# karmacontroller.net
KiCad netlist of a schematic drawn in EAGLE
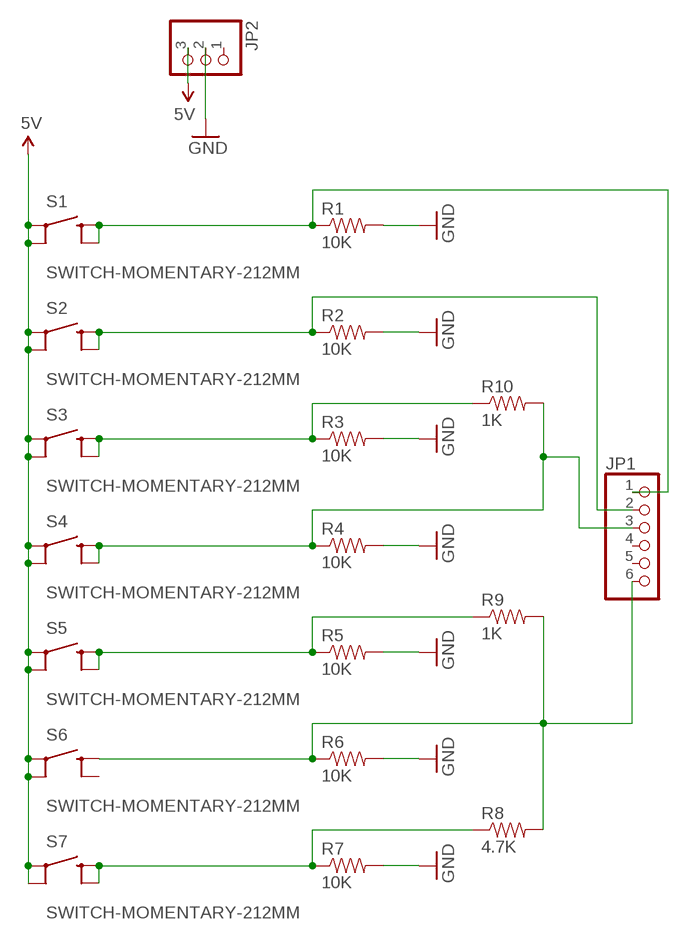
[diagram p0: schematic, sheet 1]

(export (version "E")
  (design (tool "Eeschema 10.0.6"))
  (components
    (comp (ref "JP1")
      (value "PINHD-1X6")
      (footprint "eagle-import:1X06")
      (libsource (lib "eagle-import") (part "PINHD-1X6"))
    )
    (comp (ref "JP2")
      (value "PINHD-1X3")
      (footprint "eagle-import:1X03")
      (libsource (lib "eagle-import") (part "PINHD-1X3"))
    )
    (comp (ref "R1")
      (value "10K")
      (footprint "eagle-import:AXIAL-0.3")
      (libsource (lib "eagle-import") (part "RESISTORAXIAL-0.3"))
    )
    (comp (ref "R2")
      (value "10K")
      (footprint "eagle-import:AXIAL-0.3")
      (libsource (lib "eagle-import") (part "RESISTORAXIAL-0.3"))
    )
    (comp (ref "R3")
      (value "10K")
      (footprint "eagle-import:AXIAL-0.3")
      (libsource (lib "eagle-import") (part "RESISTORAXIAL-0.3"))
    )
    (comp (ref "R4")
      (value "10K")
      (footprint "eagle-import:AXIAL-0.3")
      (libsource (lib "eagle-import") (part "RESISTORAXIAL-0.3"))
    )
    (comp (ref "R5")
      (value "10K")
      (footprint "eagle-import:AXIAL-0.3")
      (libsource (lib "eagle-import") (part "RESISTORAXIAL-0.3"))
    )
    (comp (ref "R6")
      (value "10K")
      (footprint "eagle-import:AXIAL-0.3")
      (libsource (lib "eagle-import") (part "RESISTORAXIAL-0.3"))
    )
    (comp (ref "R7")
      (value "10K")
      (footprint "eagle-import:AXIAL-0.3")
      (libsource (lib "eagle-import") (part "RESISTORAXIAL-0.3"))
    )
    (comp (ref "R8")
      (value "4.7K")
      (footprint "eagle-import:AXIAL-0.3")
      (libsource (lib "eagle-import") (part "RESISTORAXIAL-0.3"))
    )
    (comp (ref "R9")
      (value "1K")
      (footprint "eagle-import:AXIAL-0.3")
      (libsource (lib "eagle-import") (part "RESISTORAXIAL-0.3"))
    )
    (comp (ref "R10")
      (value "1K")
      (footprint "eagle-import:AXIAL-0.3")
      (libsource (lib "eagle-import") (part "RESISTORAXIAL-0.3"))
    )
    (comp (ref "S1")
      (value "SWITCH-MOMENTARY-212MM")
      (footprint "eagle-import:TACTILE-PTH-12MM")
      (libsource (lib "eagle-import") (part "SWITCH-MOMENTARY-212MM"))
    )
    (comp (ref "S2")
      (value "SWITCH-MOMENTARY-212MM")
      (footprint "eagle-import:TACTILE-PTH-12MM")
      (libsource (lib "eagle-import") (part "SWITCH-MOMENTARY-212MM"))
    )
    (comp (ref "S3")
      (value "SWITCH-MOMENTARY-212MM")
      (footprint "eagle-import:TACTILE-PTH-12MM")
      (libsource (lib "eagle-import") (part "SWITCH-MOMENTARY-212MM"))
    )
    (comp (ref "S4")
      (value "SWITCH-MOMENTARY-212MM")
      (footprint "eagle-import:TACTILE-PTH-12MM")
      (libsource (lib "eagle-import") (part "SWITCH-MOMENTARY-212MM"))
    )
    (comp (ref "S5")
      (value "SWITCH-MOMENTARY-212MM")
      (footprint "eagle-import:TACTILE-PTH-12MM")
      (libsource (lib "eagle-import") (part "SWITCH-MOMENTARY-212MM"))
    )
    (comp (ref "S6")
      (value "SWITCH-MOMENTARY-212MM")
      (footprint "eagle-import:TACTILE-PTH-12MM")
      (libsource (lib "eagle-import") (part "SWITCH-MOMENTARY-212MM"))
    )
    (comp (ref "S7")
      (value "SWITCH-MOMENTARY-212MM")
      (footprint "eagle-import:TACTILE-PTH-12MM")
      (libsource (lib "eagle-import") (part "SWITCH-MOMENTARY-212MM"))
    )
  )
  (nets
    (net (code "1") (name "5V") (class "Default")
      (node (ref "JP2") (pin "3") (pinfunction "3_3") (pintype "passive"))
      (node (ref "S1") (pin "1") (pinfunction "1_1") (pintype "passive"))
      (node (ref "S1") (pin "2") (pinfunction "1'_2") (pintype "passive"))
      (node (ref "S2") (pin "1") (pinfunction "1_1") (pintype "passive"))
      (node (ref "S2") (pin "2") (pinfunction "1'_2") (pintype "passive"))
      (node (ref "S3") (pin "1") (pinfunction "1_1") (pintype "passive"))
      (node (ref "S3") (pin "2") (pinfunction "1'_2") (pintype "passive"))
      (node (ref "S4") (pin "1") (pinfunction "1_1") (pintype "passive"))
      (node (ref "S4") (pin "2") (pinfunction "1'_2") (pintype "passive"))
      (node (ref "S5") (pin "1") (pinfunction "1_1") (pintype "passive"))
      (node (ref "S5") (pin "2") (pinfunction "1'_2") (pintype "passive"))
      (node (ref "S6") (pin "1") (pinfunction "1_1") (pintype "passive"))
      (node (ref "S6") (pin "2") (pinfunction "1'_2") (pintype "passive"))
      (node (ref "S7") (pin "1") (pinfunction "1_1") (pintype "passive"))
      (node (ref "S7") (pin "2") (pinfunction "1'_2") (pintype "passive"))
    )
    (net (code "2") (name "GND") (class "Default")
      (node (ref "JP2") (pin "2") (pinfunction "2_2") (pintype "passive"))
      (node (ref "R1") (pin "P$2") (pinfunction "2_P$2") (pintype "passive"))
      (node (ref "R2") (pin "P$2") (pinfunction "2_P$2") (pintype "passive"))
      (node (ref "R3") (pin "P$2") (pinfunction "2_P$2") (pintype "passive"))
      (node (ref "R4") (pin "P$2") (pinfunction "2_P$2") (pintype "passive"))
      (node (ref "R5") (pin "P$2") (pinfunction "2_P$2") (pintype "passive"))
      (node (ref "R6") (pin "P$2") (pinfunction "2_P$2") (pintype "passive"))
      (node (ref "R7") (pin "P$2") (pinfunction "2_P$2") (pintype "passive"))
    )
    (net (code "3") (name "Net-(R1-1)") (class "Default")
      (node (ref "JP1") (pin "1") (pinfunction "1_1") (pintype "passive"))
      (node (ref "R1") (pin "P$1") (pinfunction "1_P$1") (pintype "passive"))
      (node (ref "S1") (pin "3") (pinfunction "2_3") (pintype "passive"))
      (node (ref "S1") (pin "4") (pinfunction "2'_4") (pintype "passive"))
    )
    (net (code "4") (name "Net-(R2-1)") (class "Default")
      (node (ref "JP1") (pin "2") (pinfunction "2_2") (pintype "passive"))
      (node (ref "R2") (pin "P$1") (pinfunction "1_P$1") (pintype "passive"))
      (node (ref "S2") (pin "3") (pinfunction "2_3") (pintype "passive"))
      (node (ref "S2") (pin "4") (pinfunction "2'_4") (pintype "passive"))
    )
    (net (code "5") (name "Net-(R5-1)") (class "Default")
      (node (ref "R5") (pin "P$1") (pinfunction "1_P$1") (pintype "passive"))
      (node (ref "R9") (pin "P$1") (pinfunction "1_P$1") (pintype "passive"))
      (node (ref "S5") (pin "3") (pinfunction "2_3") (pintype "passive"))
      (node (ref "S5") (pin "4") (pinfunction "2'_4") (pintype "passive"))
    )
    (net (code "6") (name "Net-(R6-1)") (class "Default")
      (node (ref "JP1") (pin "6") (pinfunction "6_6") (pintype "passive"))
      (node (ref "R6") (pin "P$1") (pinfunction "1_P$1") (pintype "passive"))
      (node (ref "R8") (pin "P$2") (pinfunction "2_P$2") (pintype "passive"))
      (node (ref "R9") (pin "P$2") (pinfunction "2_P$2") (pintype "passive"))
      (node (ref "S6") (pin "3") (pinfunction "2_3") (pintype "passive"))
    )
    (net (code "7") (name "Net-(R7-1)") (class "Default")
      (node (ref "R7") (pin "P$1") (pinfunction "1_P$1") (pintype "passive"))
      (node (ref "R8") (pin "P$1") (pinfunction "1_P$1") (pintype "passive"))
      (node (ref "S7") (pin "3") (pinfunction "2_3") (pintype "passive"))
      (node (ref "S7") (pin "4") (pinfunction "2'_4") (pintype "passive"))
    )
    (net (code "8") (name "Net-(R10-1)") (class "Default")
      (node (ref "R10") (pin "P$1") (pinfunction "1_P$1") (pintype "passive"))
      (node (ref "R3") (pin "P$1") (pinfunction "1_P$1") (pintype "passive"))
      (node (ref "S3") (pin "3") (pinfunction "2_3") (pintype "passive"))
      (node (ref "S3") (pin "4") (pinfunction "2'_4") (pintype "passive"))
    )
    (net (code "9") (name "Net-(R10-2)") (class "Default")
      (node (ref "JP1") (pin "3") (pinfunction "3_3") (pintype "passive"))
      (node (ref "R10") (pin "P$2") (pinfunction "2_P$2") (pintype "passive"))
      (node (ref "R4") (pin "P$1") (pinfunction "1_P$1") (pintype "passive"))
      (node (ref "S4") (pin "3") (pinfunction "2_3") (pintype "passive"))
      (node (ref "S4") (pin "4") (pinfunction "2'_4") (pintype "passive"))
    )
    (net (code "10") (name "unconnected-(JP1-Pad4)") (class "Default")
      (node (ref "JP1") (pin "4") (pinfunction "4_4") (pintype "passive"))
    )
    (net (code "11") (name "unconnected-(JP1-Pad5)") (class "Default")
      (node (ref "JP1") (pin "5") (pinfunction "5_5") (pintype "passive"))
    )
    (net (code "12") (name "unconnected-(JP2-Pad1)") (class "Default")
      (node (ref "JP2") (pin "1") (pinfunction "1_1") (pintype "passive"))
    )
    (net (code "13") (name "unconnected-(S6-2'-Pad4)") (class "Default")
      (node (ref "S6") (pin "4") (pinfunction "2'_4") (pintype "passive"))
    )
  )
)
